# ATMEGA8A.net
KiCad netlist of a schematic drawn in Altium Designer
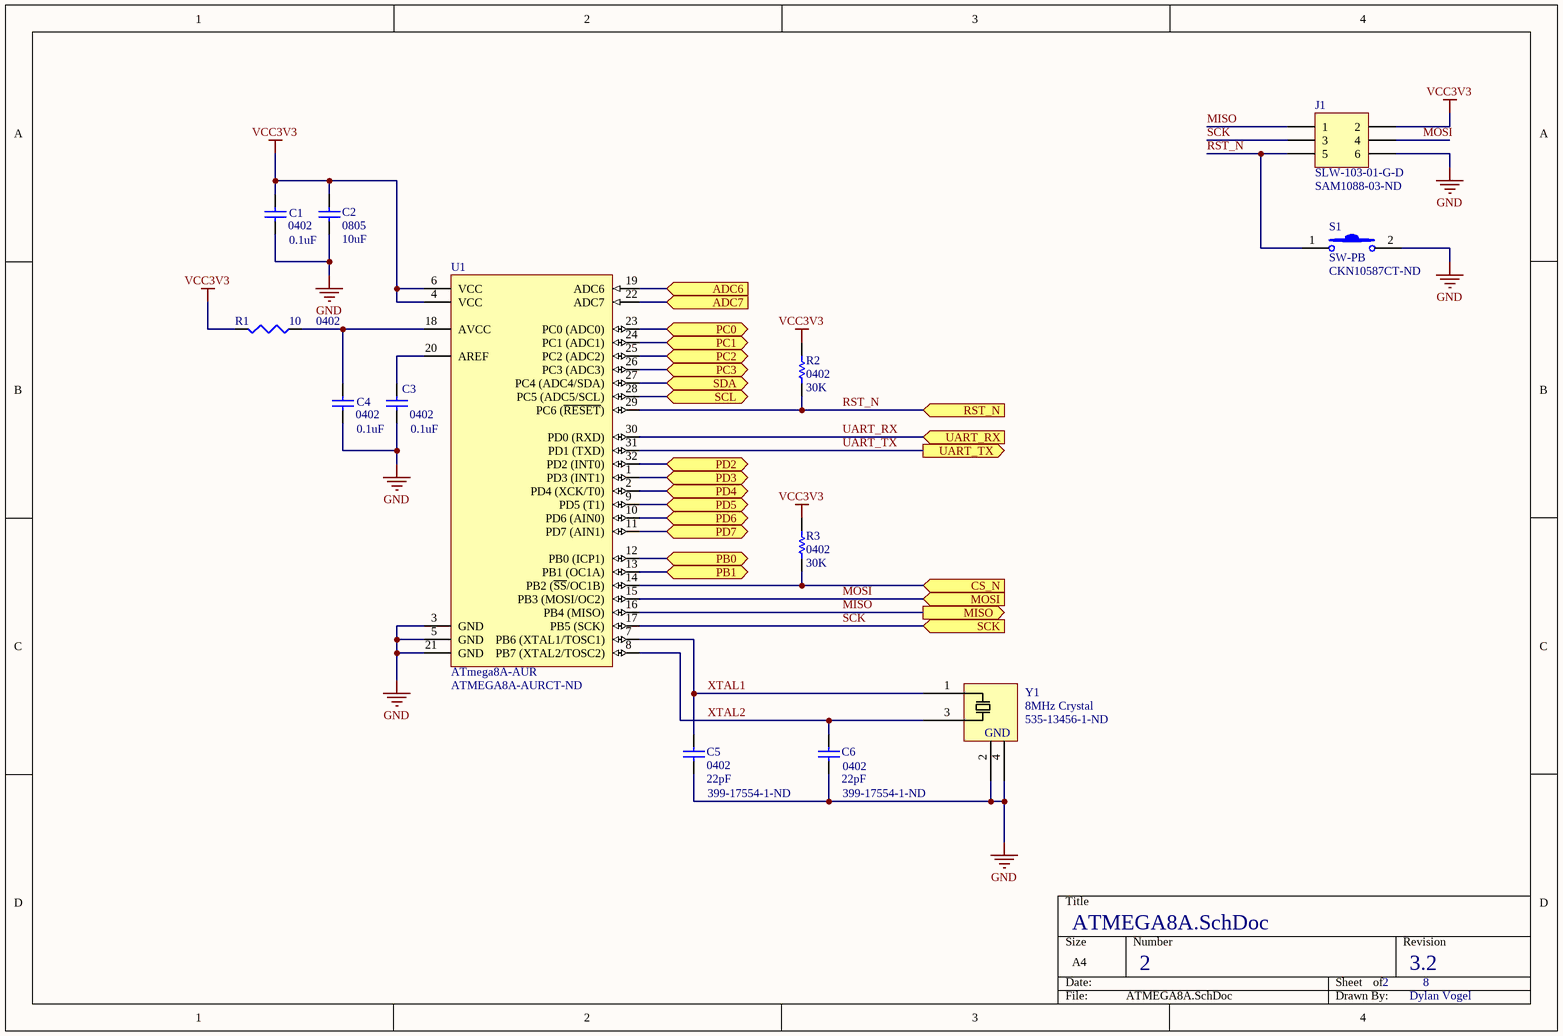
[diagram p0: ATMEGA8A.SchDoc]

(export (version "E")
  (design (tool "Eeschema 10.0.6"))
  (components
    (comp (ref "C1")
      (value "0402")
      (footprint "CAP0402R")
      (description "Capacitor (Semiconductor SIM Model)")
      (fields
        (field (name "ALTIUM_VALUE") "0.1uF")
        (field (name "MANUFACTURER") "Murata")
        (field (name "MANUFACTURER PART NUMBER") "GCM155R71C104KA55J")
        (field (name "PUBLISHER") "Altium Limited")
      )
      (libsource (lib "Miscellaneous Devices") (part "Cap Semi"))
    )
    (comp (ref "C2")
      (value "0805")
      (footprint "CAP0805R")
      (description "Capacitor")
      (fields
        (field (name "ALTIUM_VALUE") "10uF")
        (field (name "MANUFACTURER") "TDK")
        (field (name "MANUFACTURER PART NUMBER") "CGA4J1X7R0J106K125AC")
        (field (name "PUBLISHER") "Altium Limited")
      )
      (libsource (lib "Miscellaneous Devices") (part "Cap"))
    )
    (comp (ref "C3")
      (value "0402")
      (footprint "CAP0402R")
      (description "Capacitor (Semiconductor SIM Model)")
      (fields
        (field (name "ALTIUM_VALUE") "0.1uF")
        (field (name "MANUFACTURER") "Murata")
        (field (name "MANUFACTURER PART NUMBER") "GCM155R71C104KA55J")
        (field (name "PUBLISHER") "Altium Limited")
      )
      (libsource (lib "Miscellaneous Devices") (part "Cap Semi"))
    )
    (comp (ref "C4")
      (value "0402")
      (footprint "CAP0402R")
      (description "Capacitor (Semiconductor SIM Model)")
      (fields
        (field (name "ALTIUM_VALUE") "0.1uF")
        (field (name "MANUFACTURER") "Murata")
        (field (name "MANUFACTURER PART NUMBER") "GCM155R71C104KA55J")
        (field (name "PUBLISHER") "Altium Limited")
      )
      (libsource (lib "Miscellaneous Devices") (part "Cap Semi"))
    )
    (comp (ref "C5")
      (value "0402")
      (footprint "CAP0402R")
      (description "Capacitor")
      (fields
        (field (name "ALTIUM_VALUE") "22pF")
        (field (name "SUPPLIER PART NUMBER 1") "399-17554-1-ND")
        (field (name "MANUFACTURER") "KEMET")
        (field (name "MANUFACTURER PART NUMBER") "C0402C220K4RAC7867")
        (field (name "PUBLISHER") "Altium Limited")
      )
      (libsource (lib "Miscellaneous Devices") (part "Cap"))
    )
    (comp (ref "C6")
      (value "0402")
      (footprint "CAP0402R")
      (description "Capacitor")
      (fields
        (field (name "ALTIUM_VALUE") "22pF")
        (field (name "SUPPLIER PART NUMBER 1") "399-17554-1-ND")
        (field (name "MANUFACTURER") "KEMET")
        (field (name "MANUFACTURER PART NUMBER") "C0402C220K4RAC7867")
        (field (name "PUBLISHER") "Altium Limited")
      )
      (libsource (lib "Miscellaneous Devices") (part "Cap"))
    )
    (comp (ref "J1")
      (value "SLW-103-01-G-D")
      (footprint "SLW-103-01-X-D")
      (fields (field (name "SUPPLIER PART NUMBER 1") "SAM1088-03-ND"))
      (libsource (lib "heron-general") (part "SLW-103-01-G-D"))
    )
    (comp (ref "R1")
      (value "0402")
      (footprint "RES0402R")
      (description "Resistor")
      (fields (field (name "ALTIUM_VALUE") "10") (field (name "PUBLISHER") "Altium Limited"))
      (libsource (lib "Miscellaneous Devices") (part "Res3"))
    )
    (comp (ref "R2")
      (value "0402")
      (footprint "RES0402R")
      (description "Resistor")
      (fields (field (name "ALTIUM_VALUE") "30K") (field (name "PUBLISHER") "Altium Limited"))
      (libsource (lib "Miscellaneous Devices") (part "Res1"))
    )
    (comp (ref "R3")
      (value "0402")
      (footprint "RES0402R")
      (description "Resistor")
      (fields (field (name "ALTIUM_VALUE") "30K") (field (name "PUBLISHER") "Altium Limited"))
      (libsource (lib "Miscellaneous Devices") (part "Res1"))
    )
    (comp (ref "S1")
      (value "SW-PB")
      (footprint "PTS830GM140 SMTR LFS - Pushbutton")
      (description "Schematic symbol for a generic 2-pin pushbutton, OFF-mom.")
      (fields (field (name "SUPPLIER PART NUMBER 1") "CKN10587CT-ND"))
      (libsource (lib "SwitchesButtons") (part "Pushbutton - Low Profile"))
    )
    (comp (ref "U1")
      (value "ATmega8A-AUR")
      (footprint "QFP80P900X900X120-32")
      (fields
        (field (name "PARTNUMBER") "ATMEGA8A-AUR")
        (field (name "SUPPLIER PART NUMBER 1") "ATMEGA8A-AURCT-ND")
      )
      (libsource (lib "heron-general") (part "ATMEGA8A-AUR"))
    )
    (comp (ref "Y1")
      (value "8MHz Crystal")
      (footprint "OSCSC500X320X110-4N")
      (description "8MHz Abracom 4-pin crystal.")
      (fields (field (name "SUPPLIER PART NUMBER 1") "535-13456-1-ND"))
      (libsource (lib "heron-general") (part "AMB3B-8MHz"))
    )
  )
  (nets
    (net (code "1") (name "/ADC6") (class "Default")
      (node (ref "U1") (pin "19") (pinfunction "ADC6_19") (pintype "input"))
    )
    (net (code "2") (name "/ADC7") (class "Default")
      (node (ref "U1") (pin "22") (pinfunction "ADC7_22") (pintype "input"))
    )
    (net (code "3") (name "/CS_N") (class "Default")
      (node (ref "R3") (pin "1") (pinfunction "1_1") (pintype "passive"))
      (node (ref "U1") (pin "14") (pinfunction "PB2_(~{SS}/OC1B)_14") (pintype "bidirectional"))
    )
    (net (code "4") (name "/MISO") (class "Default")
      (node (ref "J1") (pin "1") (pinfunction "1_1") (pintype "passive"))
      (node (ref "U1") (pin "16") (pinfunction "PB4_(MISO)_16") (pintype "bidirectional"))
    )
    (net (code "5") (name "/MOSI") (class "Default")
      (node (ref "J1") (pin "4") (pinfunction "4_4") (pintype "passive"))
      (node (ref "U1") (pin "15") (pinfunction "PB3_(MOSI/OC2)_15") (pintype "bidirectional"))
    )
    (net (code "6") (name "/PB0") (class "Default")
      (node (ref "U1") (pin "12") (pinfunction "PB0_(ICP1)_12") (pintype "bidirectional"))
    )
    (net (code "7") (name "/PB1") (class "Default")
      (node (ref "U1") (pin "13") (pinfunction "PB1_(OC1A)_13") (pintype "bidirectional"))
    )
    (net (code "8") (name "/PC0") (class "Default")
      (node (ref "U1") (pin "23") (pinfunction "PC0_(ADC0)_23") (pintype "bidirectional"))
    )
    (net (code "9") (name "/PC1") (class "Default")
      (node (ref "U1") (pin "24") (pinfunction "PC1_(ADC1)_24") (pintype "bidirectional"))
    )
    (net (code "10") (name "/PC2") (class "Default")
      (node (ref "U1") (pin "25") (pinfunction "PC2_(ADC2)_25") (pintype "bidirectional"))
    )
    (net (code "11") (name "/PC3") (class "Default")
      (node (ref "U1") (pin "26") (pinfunction "PC3_(ADC3)_26") (pintype "bidirectional"))
    )
    (net (code "12") (name "/PD2") (class "Default")
      (node (ref "U1") (pin "32") (pinfunction "PD2_(INT0)_32") (pintype "bidirectional"))
    )
    (net (code "13") (name "/PD3") (class "Default")
      (node (ref "U1") (pin "1") (pinfunction "PD3_(INT1)_1") (pintype "bidirectional"))
    )
    (net (code "14") (name "/PD4") (class "Default")
      (node (ref "U1") (pin "2") (pinfunction "PD4_(XCK/T0)_2") (pintype "bidirectional"))
    )
    (net (code "15") (name "/PD5") (class "Default")
      (node (ref "U1") (pin "9") (pinfunction "PD5_(T1)_9") (pintype "bidirectional"))
    )
    (net (code "16") (name "/PD6") (class "Default")
      (node (ref "U1") (pin "10") (pinfunction "PD6_(AIN0)_10") (pintype "bidirectional"))
    )
    (net (code "17") (name "/PD7") (class "Default")
      (node (ref "U1") (pin "11") (pinfunction "PD7_(AIN1)_11") (pintype "bidirectional"))
    )
    (net (code "18") (name "/RST_N") (class "Default")
      (node (ref "J1") (pin "5") (pinfunction "5_5") (pintype "passive"))
      (node (ref "R2") (pin "1") (pinfunction "1_1") (pintype "passive"))
      (node (ref "S1") (pin "1") (pinfunction "1_1") (pintype "passive"))
      (node (ref "U1") (pin "29") (pinfunction "PC6_(~{RESET})_29") (pintype "bidirectional"))
    )
    (net (code "19") (name "/SCK") (class "Default")
      (node (ref "J1") (pin "3") (pinfunction "3_3") (pintype "passive"))
      (node (ref "U1") (pin "17") (pinfunction "PB5_(SCK)_17") (pintype "bidirectional"))
    )
    (net (code "20") (name "/SCL") (class "Default")
      (node (ref "U1") (pin "28") (pinfunction "PC5_(ADC5/SCL)_28") (pintype "bidirectional"))
    )
    (net (code "21") (name "/SDA") (class "Default")
      (node (ref "U1") (pin "27") (pinfunction "PC4_(ADC4/SDA)_27") (pintype "bidirectional"))
    )
    (net (code "22") (name "/UART_RX") (class "Default")
      (node (ref "U1") (pin "30") (pinfunction "PD0_(RXD)_30") (pintype "bidirectional"))
    )
    (net (code "23") (name "/UART_TX") (class "Default")
      (node (ref "U1") (pin "31") (pinfunction "PD1_(TXD)_31") (pintype "bidirectional"))
    )
    (net (code "24") (name "/XTAL1") (class "Default")
      (node (ref "C5") (pin "2") (pinfunction "2_2") (pintype "passive"))
      (node (ref "U1") (pin "7") (pinfunction "PB6_(XTAL1/TOSC1)_7") (pintype "bidirectional"))
      (node (ref "Y1") (pin "1") (pinfunction "IN_1") (pintype "passive"))
    )
    (net (code "25") (name "/XTAL2") (class "Default")
      (node (ref "C6") (pin "2") (pinfunction "2_2") (pintype "passive"))
      (node (ref "U1") (pin "8") (pinfunction "PB7_(XTAL2/TOSC2)_8") (pintype "bidirectional"))
      (node (ref "Y1") (pin "3") (pinfunction "IN_3") (pintype "passive"))
    )
    (net (code "26") (name "GND") (class "Default")
      (node (ref "C1") (pin "1") (pinfunction "1_1") (pintype "passive"))
      (node (ref "C2") (pin "1") (pinfunction "1_1") (pintype "passive"))
      (node (ref "C3") (pin "1") (pinfunction "1_1") (pintype "passive"))
      (node (ref "C4") (pin "1") (pinfunction "1_1") (pintype "passive"))
      (node (ref "C5") (pin "1") (pinfunction "1_1") (pintype "passive"))
      (node (ref "C6") (pin "1") (pinfunction "1_1") (pintype "passive"))
      (node (ref "J1") (pin "6") (pinfunction "6_6") (pintype "passive"))
      (node (ref "S1") (pin "2") (pinfunction "2_2") (pintype "passive"))
      (node (ref "U1") (pin "21") (pinfunction "GND_21") (pintype "power_in"))
      (node (ref "U1") (pin "3") (pinfunction "GND_3") (pintype "power_in"))
      (node (ref "U1") (pin "5") (pinfunction "GND_5") (pintype "power_in"))
      (node (ref "Y1") (pin "2") (pinfunction "5_2") (pintype "passive"))
      (node (ref "Y1") (pin "4") (pinfunction "4_4") (pintype "passive"))
    )
    (net (code "27") (name "Net-(U1-AREF)") (class "Default")
      (node (ref "C3") (pin "2") (pinfunction "2_2") (pintype "passive"))
      (node (ref "U1") (pin "20") (pinfunction "AREF_20") (pintype "power_in"))
    )
    (net (code "28") (name "Net-(U1-AVCC)") (class "Default")
      (node (ref "C4") (pin "2") (pinfunction "2_2") (pintype "passive"))
      (node (ref "R1") (pin "1") (pinfunction "1_1") (pintype "passive"))
      (node (ref "U1") (pin "18") (pinfunction "AVCC_18") (pintype "power_in"))
    )
    (net (code "29") (name "VCC3V3") (class "Default")
      (node (ref "C1") (pin "2") (pinfunction "2_2") (pintype "passive"))
      (node (ref "C2") (pin "2") (pinfunction "2_2") (pintype "passive"))
      (node (ref "J1") (pin "2") (pinfunction "2_2") (pintype "passive"))
      (node (ref "R1") (pin "2") (pinfunction "2_2") (pintype "passive"))
      (node (ref "R2") (pin "2") (pinfunction "2_2") (pintype "passive"))
      (node (ref "R3") (pin "2") (pinfunction "2_2") (pintype "passive"))
      (node (ref "U1") (pin "4") (pinfunction "VCC_4") (pintype "power_in"))
      (node (ref "U1") (pin "6") (pinfunction "VCC_6") (pintype "power_in"))
    )
  )
)
